# CPU.net
KiCad netlist of a schematic drawn in Altium Designer
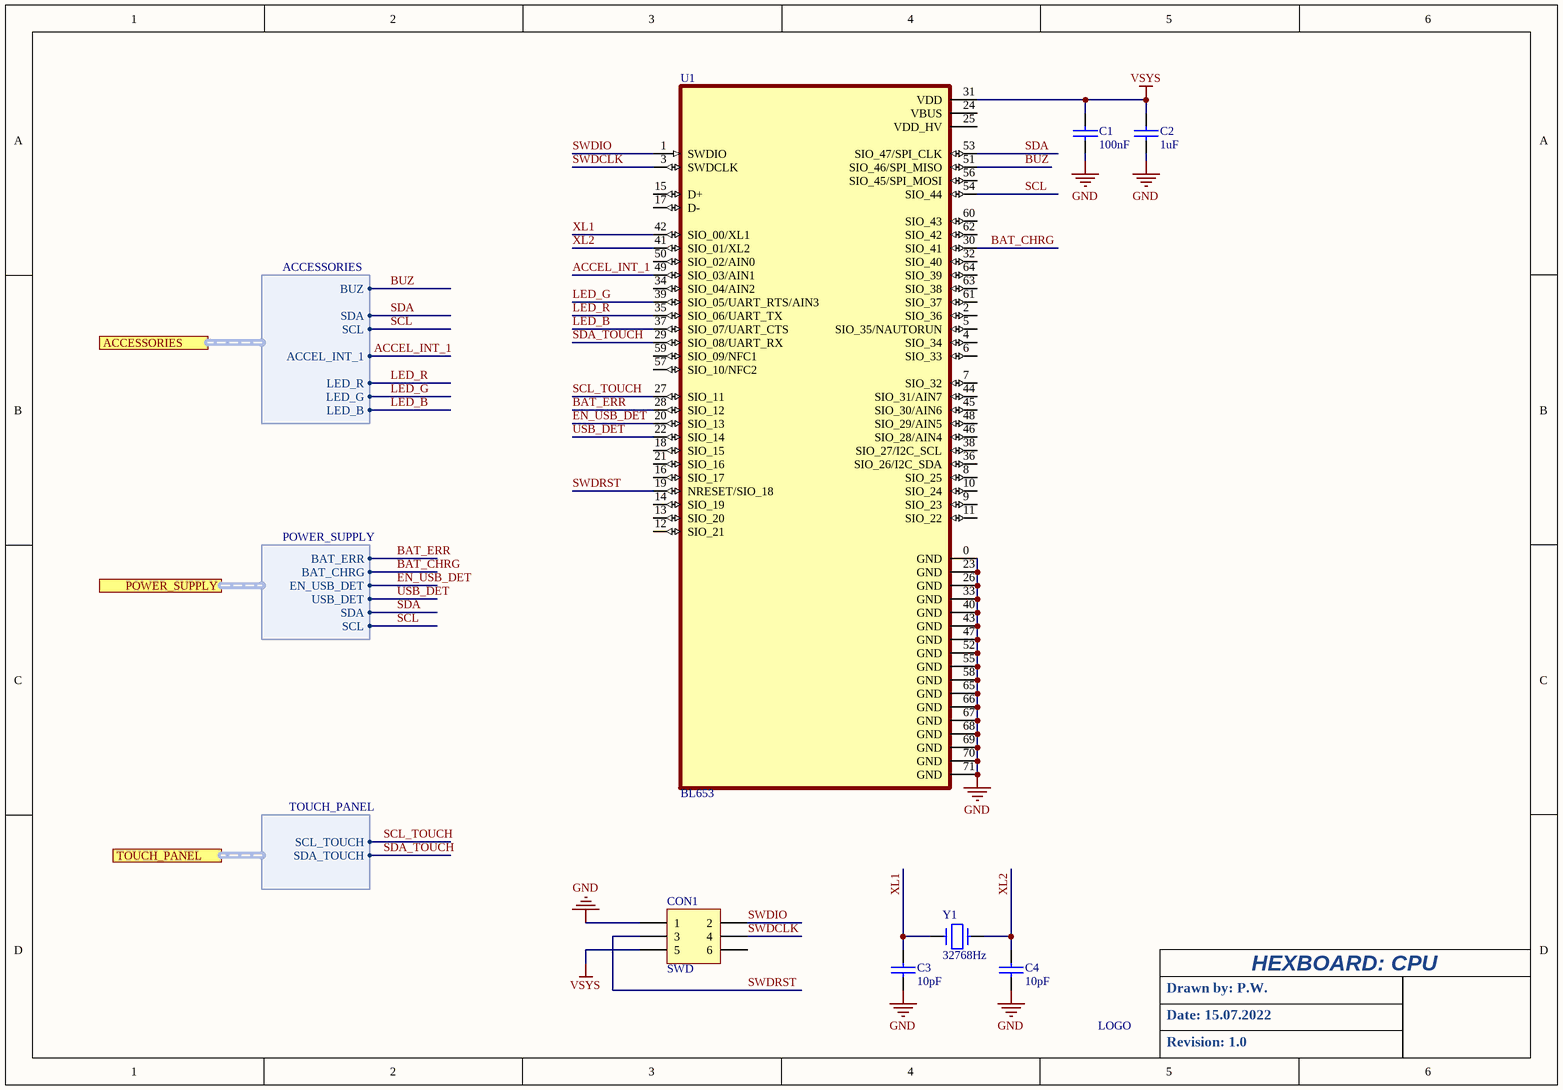
[diagram p0: CPU.SchDoc]

(export (version "E")
  (design (tool "Eeschema 10.0.6"))
  (components
    (comp (ref "*1") (value "LOGO") (footprint "NEWLOGO2") (libsource (lib "LIB_PW") (part "LOGO")))
    (comp (ref "C1")
      (value "100nF")
      (footprint "C0603L")
      (description "Capacitor")
      (libsource (lib "LIB_PW") (part "CAP"))
    )
    (comp (ref "C2")
      (value "1uF")
      (footprint "C0603L")
      (description "Capacitor")
      (libsource (lib "LIB_PW") (part "CAP"))
    )
    (comp (ref "C3")
      (value "10pF")
      (footprint "C0603L")
      (description "Capacitor")
      (libsource (lib "SCH_PW") (part "CAP"))
    )
    (comp (ref "C4")
      (value "10pF")
      (footprint "C0603L")
      (description "Capacitor")
      (libsource (lib "SCH_PW") (part "CAP"))
    )
    (comp (ref "CON1")
      (value "SWD")
      (footprint "HDR2x3_1mm27")
      (description "Header, 3-Pin, Dual row")
      (fields (field (name "PUBLISHER") "Altium Limited"))
      (libsource (lib "LIB_PW") (part "Header 3X2"))
    )
    (comp (ref "U1")
      (value "BL653")
      (footprint "BL653")
      (fields
        (field (name "DIGI-KEY_PART_NUMBER") "451-00001CT-ND")
        (field (name "MP") "451-00001")
        (field (name "MF") "Laird -")
      )
      (libsource (lib "LIB_PW") (part "BL653"))
    )
    (comp (ref "Y1")
      (value "32768Hz")
      (footprint "X_FC-13F")
      (description "Crystal")
      (libsource (lib "SCH_PW") (part "CRYSTAL"))
    )
  )
  (nets
    (net (code "4") (name "/ACCEL_INT_1") (class "Default")
      (node (ref "U1") (pin "49") (pinfunction "SIO_03/AIN1_49") (pintype "bidirectional"))
    )
    (net (code "5") (name "/BAT_CHRG") (class "Default")
      (node (ref "U1") (pin "30") (pinfunction "SIO_41_30") (pintype "bidirectional"))
    )
    (net (code "6") (name "/BAT_ERR") (class "Default")
      (node (ref "U1") (pin "28") (pinfunction "SIO_12_28") (pintype "bidirectional"))
    )
    (net (code "7") (name "/BUZ") (class "Default")
      (node (ref "U1") (pin "51") (pinfunction "SIO_46/SPI_MISO_51") (pintype "bidirectional"))
    )
    (net (code "8") (name "/EN_USB_DET") (class "Default")
      (node (ref "U1") (pin "20") (pinfunction "SIO_13_20") (pintype "bidirectional"))
    )
    (net (code "9") (name "/LED_B") (class "Default")
      (node (ref "U1") (pin "37") (pinfunction "SIO_07/UART_CTS_37") (pintype "bidirectional"))
    )
    (net (code "10") (name "/LED_G") (class "Default")
      (node (ref "U1") (pin "39") (pinfunction "SIO_05/UART_RTS/AIN3_39") (pintype "bidirectional"))
    )
    (net (code "11") (name "/LED_R") (class "Default")
      (node (ref "U1") (pin "35") (pinfunction "SIO_06/UART_TX_35") (pintype "bidirectional"))
    )
    (net (code "12") (name "/SCL") (class "Default")
      (node (ref "U1") (pin "54") (pinfunction "SIO_44_54") (pintype "bidirectional"))
    )
    (net (code "13") (name "/SCL_TOUCH") (class "Default")
      (node (ref "U1") (pin "27") (pinfunction "SIO_11_27") (pintype "bidirectional"))
    )
    (net (code "14") (name "/SDA") (class "Default")
      (node (ref "U1") (pin "53") (pinfunction "SIO_47/SPI_CLK_53") (pintype "bidirectional"))
    )
    (net (code "15") (name "/SDA_TOUCH") (class "Default")
      (node (ref "U1") (pin "29") (pinfunction "SIO_08/UART_RX_29") (pintype "bidirectional"))
    )
    (net (code "16") (name "/SWDCLK") (class "Default")
      (node (ref "CON1") (pin "4") (pinfunction "4_4") (pintype "passive"))
      (node (ref "U1") (pin "3") (pinfunction "SWDCLK_3") (pintype "bidirectional"))
    )
    (net (code "17") (name "/SWDIO") (class "Default")
      (node (ref "CON1") (pin "2") (pinfunction "2_2") (pintype "passive"))
      (node (ref "U1") (pin "1") (pinfunction "SWDIO_1") (pintype "input"))
    )
    (net (code "18") (name "/SWDRST") (class "Default")
      (node (ref "CON1") (pin "3") (pinfunction "3_3") (pintype "passive"))
      (node (ref "U1") (pin "19") (pinfunction "NRESET/SIO_18_19") (pintype "bidirectional"))
    )
    (net (code "19") (name "/USB_DET") (class "Default")
      (node (ref "U1") (pin "22") (pinfunction "SIO_14_22") (pintype "bidirectional"))
    )
    (net (code "20") (name "/XL1") (class "Default")
      (node (ref "C3") (pin "1") (pinfunction "1_1") (pintype "passive"))
      (node (ref "U1") (pin "42") (pinfunction "SIO_00/XL1_42") (pintype "bidirectional"))
      (node (ref "Y1") (pin "1") (pinfunction "1_1") (pintype "passive"))
    )
    (net (code "21") (name "/XL2") (class "Default")
      (node (ref "C4") (pin "1") (pinfunction "1_1") (pintype "passive"))
      (node (ref "U1") (pin "41") (pinfunction "SIO_01/XL2_41") (pintype "bidirectional"))
      (node (ref "Y1") (pin "2") (pinfunction "2_2") (pintype "passive"))
    )
    (net (code "25") (name "GND") (class "Default")
      (node (ref "C1") (pin "2") (pinfunction "2_2") (pintype "passive"))
      (node (ref "C2") (pin "2") (pinfunction "2_2") (pintype "passive"))
      (node (ref "C3") (pin "2") (pinfunction "2_2") (pintype "passive"))
      (node (ref "C4") (pin "2") (pinfunction "2_2") (pintype "passive"))
      (node (ref "CON1") (pin "1") (pinfunction "1_1") (pintype "passive"))
      (node (ref "U1") (pin "0") (pinfunction "GND_0") (pintype "power_in"))
      (node (ref "U1") (pin "23") (pinfunction "GND_23") (pintype "power_in"))
      (node (ref "U1") (pin "26") (pinfunction "GND_26") (pintype "power_in"))
      (node (ref "U1") (pin "33") (pinfunction "GND_33") (pintype "power_in"))
      (node (ref "U1") (pin "40") (pinfunction "GND_40") (pintype "power_in"))
      (node (ref "U1") (pin "43") (pinfunction "GND_43") (pintype "power_in"))
      (node (ref "U1") (pin "47") (pinfunction "GND_47") (pintype "power_in"))
      (node (ref "U1") (pin "52") (pinfunction "GND_52") (pintype "power_in"))
      (node (ref "U1") (pin "55") (pinfunction "GND_55") (pintype "power_in"))
      (node (ref "U1") (pin "58") (pinfunction "GND_58") (pintype "power_in"))
      (node (ref "U1") (pin "65") (pinfunction "GND_65") (pintype "power_in"))
      (node (ref "U1") (pin "66") (pinfunction "GND_66") (pintype "power_in"))
      (node (ref "U1") (pin "67") (pinfunction "GND_67") (pintype "power_in"))
      (node (ref "U1") (pin "68") (pinfunction "GND_68") (pintype "power_in"))
      (node (ref "U1") (pin "69") (pinfunction "GND_69") (pintype "power_in"))
      (node (ref "U1") (pin "70") (pinfunction "GND_70") (pintype "power_in"))
      (node (ref "U1") (pin "71") (pinfunction "GND_71") (pintype "power_in"))
    )
    (net (code "26") (name "VSYS") (class "Default")
      (node (ref "C1") (pin "1") (pinfunction "1_1") (pintype "passive"))
      (node (ref "C2") (pin "1") (pinfunction "1_1") (pintype "passive"))
      (node (ref "CON1") (pin "5") (pinfunction "5_5") (pintype "passive"))
      (node (ref "U1") (pin "31") (pinfunction "VDD_31") (pintype "power_in"))
    )
    (net (code "27") (name "unconnected-(CON1-Pad6)") (class "Default")
      (node (ref "CON1") (pin "6") (pinfunction "6_6") (pintype "passive"))
    )
    (net (code "28") (name "unconnected-(U1-D+-Pad15)") (class "Default")
      (node (ref "U1") (pin "15") (pinfunction "D+_15") (pintype "bidirectional"))
    )
    (net (code "29") (name "unconnected-(U1-D--Pad17)") (class "Default")
      (node (ref "U1") (pin "17") (pinfunction "D-_17") (pintype "bidirectional"))
    )
    (net (code "30") (name "unconnected-(U1-SIO_02{slash}AIN0-Pad50)") (class "Default")
      (node (ref "U1") (pin "50") (pinfunction "SIO_02/AIN0_50") (pintype "bidirectional"))
    )
    (net (code "31") (name "unconnected-(U1-SIO_04{slash}AIN2-Pad34)") (class "Default")
      (node (ref "U1") (pin "34") (pinfunction "SIO_04/AIN2_34") (pintype "bidirectional"))
    )
    (net (code "32") (name "unconnected-(U1-SIO_09{slash}NFC1-Pad59)") (class "Default")
      (node (ref "U1") (pin "59") (pinfunction "SIO_09/NFC1_59") (pintype "bidirectional"))
    )
    (net (code "33") (name "unconnected-(U1-SIO_10{slash}NFC2-Pad57)") (class "Default")
      (node (ref "U1") (pin "57") (pinfunction "SIO_10/NFC2_57") (pintype "bidirectional"))
    )
    (net (code "34") (name "unconnected-(U1-SIO_15-Pad18)") (class "Default")
      (node (ref "U1") (pin "18") (pinfunction "SIO_15_18") (pintype "bidirectional"))
    )
    (net (code "35") (name "unconnected-(U1-SIO_16-Pad21)") (class "Default")
      (node (ref "U1") (pin "21") (pinfunction "SIO_16_21") (pintype "bidirectional"))
    )
    (net (code "36") (name "unconnected-(U1-SIO_17-Pad16)") (class "Default")
      (node (ref "U1") (pin "16") (pinfunction "SIO_17_16") (pintype "bidirectional"))
    )
    (net (code "37") (name "unconnected-(U1-SIO_19-Pad14)") (class "Default")
      (node (ref "U1") (pin "14") (pinfunction "SIO_19_14") (pintype "bidirectional"))
    )
    (net (code "38") (name "unconnected-(U1-SIO_20-Pad13)") (class "Default")
      (node (ref "U1") (pin "13") (pinfunction "SIO_20_13") (pintype "bidirectional"))
    )
    (net (code "39") (name "unconnected-(U1-SIO_21-Pad12)") (class "Default")
      (node (ref "U1") (pin "12") (pinfunction "SIO_21_12") (pintype "bidirectional"))
    )
    (net (code "40") (name "unconnected-(U1-SIO_22-Pad11)") (class "Default")
      (node (ref "U1") (pin "11") (pinfunction "SIO_22_11") (pintype "bidirectional"))
    )
    (net (code "41") (name "unconnected-(U1-SIO_23-Pad9)") (class "Default")
      (node (ref "U1") (pin "9") (pinfunction "SIO_23_9") (pintype "bidirectional"))
    )
    (net (code "42") (name "unconnected-(U1-SIO_24-Pad10)") (class "Default")
      (node (ref "U1") (pin "10") (pinfunction "SIO_24_10") (pintype "bidirectional"))
    )
    (net (code "43") (name "unconnected-(U1-SIO_25-Pad8)") (class "Default")
      (node (ref "U1") (pin "8") (pinfunction "SIO_25_8") (pintype "bidirectional"))
    )
    (net (code "44") (name "unconnected-(U1-SIO_26{slash}I2C_SDA-Pad36)") (class "Default")
      (node (ref "U1") (pin "36") (pinfunction "SIO_26/I2C_SDA_36") (pintype "bidirectional"))
    )
    (net (code "45") (name "unconnected-(U1-SIO_27{slash}I2C_SCL-Pad38)") (class "Default")
      (node (ref "U1") (pin "38") (pinfunction "SIO_27/I2C_SCL_38") (pintype "bidirectional"))
    )
    (net (code "46") (name "unconnected-(U1-SIO_28{slash}AIN4-Pad46)") (class "Default")
      (node (ref "U1") (pin "46") (pinfunction "SIO_28/AIN4_46") (pintype "bidirectional"))
    )
    (net (code "47") (name "unconnected-(U1-SIO_29{slash}AIN5-Pad48)") (class "Default")
      (node (ref "U1") (pin "48") (pinfunction "SIO_29/AIN5_48") (pintype "bidirectional"))
    )
    (net (code "48") (name "unconnected-(U1-SIO_30{slash}AIN6-Pad45)") (class "Default")
      (node (ref "U1") (pin "45") (pinfunction "SIO_30/AIN6_45") (pintype "bidirectional"))
    )
    (net (code "49") (name "unconnected-(U1-SIO_31{slash}AIN7-Pad44)") (class "Default")
      (node (ref "U1") (pin "44") (pinfunction "SIO_31/AIN7_44") (pintype "bidirectional"))
    )
    (net (code "50") (name "unconnected-(U1-SIO_32-Pad7)") (class "Default")
      (node (ref "U1") (pin "7") (pinfunction "SIO_32_7") (pintype "bidirectional"))
    )
    (net (code "51") (name "unconnected-(U1-SIO_33-Pad6)") (class "Default")
      (node (ref "U1") (pin "6") (pinfunction "SIO_33_6") (pintype "bidirectional"))
    )
    (net (code "52") (name "unconnected-(U1-SIO_34-Pad4)") (class "Default")
      (node (ref "U1") (pin "4") (pinfunction "SIO_34_4") (pintype "bidirectional"))
    )
    (net (code "53") (name "unconnected-(U1-SIO_35{slash}NAUTORUN-Pad5)") (class "Default")
      (node (ref "U1") (pin "5") (pinfunction "SIO_35/NAUTORUN_5") (pintype "bidirectional"))
    )
    (net (code "54") (name "unconnected-(U1-SIO_36-Pad2)") (class "Default")
      (node (ref "U1") (pin "2") (pinfunction "SIO_36_2") (pintype "bidirectional"))
    )
    (net (code "55") (name "unconnected-(U1-SIO_37-Pad61)") (class "Default")
      (node (ref "U1") (pin "61") (pinfunction "SIO_37_61") (pintype "bidirectional"))
    )
    (net (code "56") (name "unconnected-(U1-SIO_38-Pad63)") (class "Default")
      (node (ref "U1") (pin "63") (pinfunction "SIO_38_63") (pintype "bidirectional"))
    )
    (net (code "57") (name "unconnected-(U1-SIO_39-Pad64)") (class "Default")
      (node (ref "U1") (pin "64") (pinfunction "SIO_39_64") (pintype "bidirectional"))
    )
    (net (code "58") (name "unconnected-(U1-SIO_40-Pad32)") (class "Default")
      (node (ref "U1") (pin "32") (pinfunction "SIO_40_32") (pintype "bidirectional"))
    )
    (net (code "59") (name "unconnected-(U1-SIO_42-Pad62)") (class "Default")
      (node (ref "U1") (pin "62") (pinfunction "SIO_42_62") (pintype "bidirectional"))
    )
    (net (code "60") (name "unconnected-(U1-SIO_43-Pad60)") (class "Default")
      (node (ref "U1") (pin "60") (pinfunction "SIO_43_60") (pintype "bidirectional"))
    )
    (net (code "61") (name "unconnected-(U1-SIO_45{slash}SPI_MOSI-Pad56)") (class "Default")
      (node (ref "U1") (pin "56") (pinfunction "SIO_45/SPI_MOSI_56") (pintype "bidirectional"))
    )
    (net (code "62") (name "unconnected-(U1-VBUS-Pad24)") (class "Default")
      (node (ref "U1") (pin "24") (pinfunction "VBUS_24") (pintype "power_in"))
    )
    (net (code "63") (name "unconnected-(U1-VDD_HV-Pad25)") (class "Default")
      (node (ref "U1") (pin "25") (pinfunction "VDD_HV_25") (pintype "power_in"))
    )
  )
)
